# BRGTC6_Dual_Daughter.net
KiCad netlist of a schematic drawn in Altium Designer
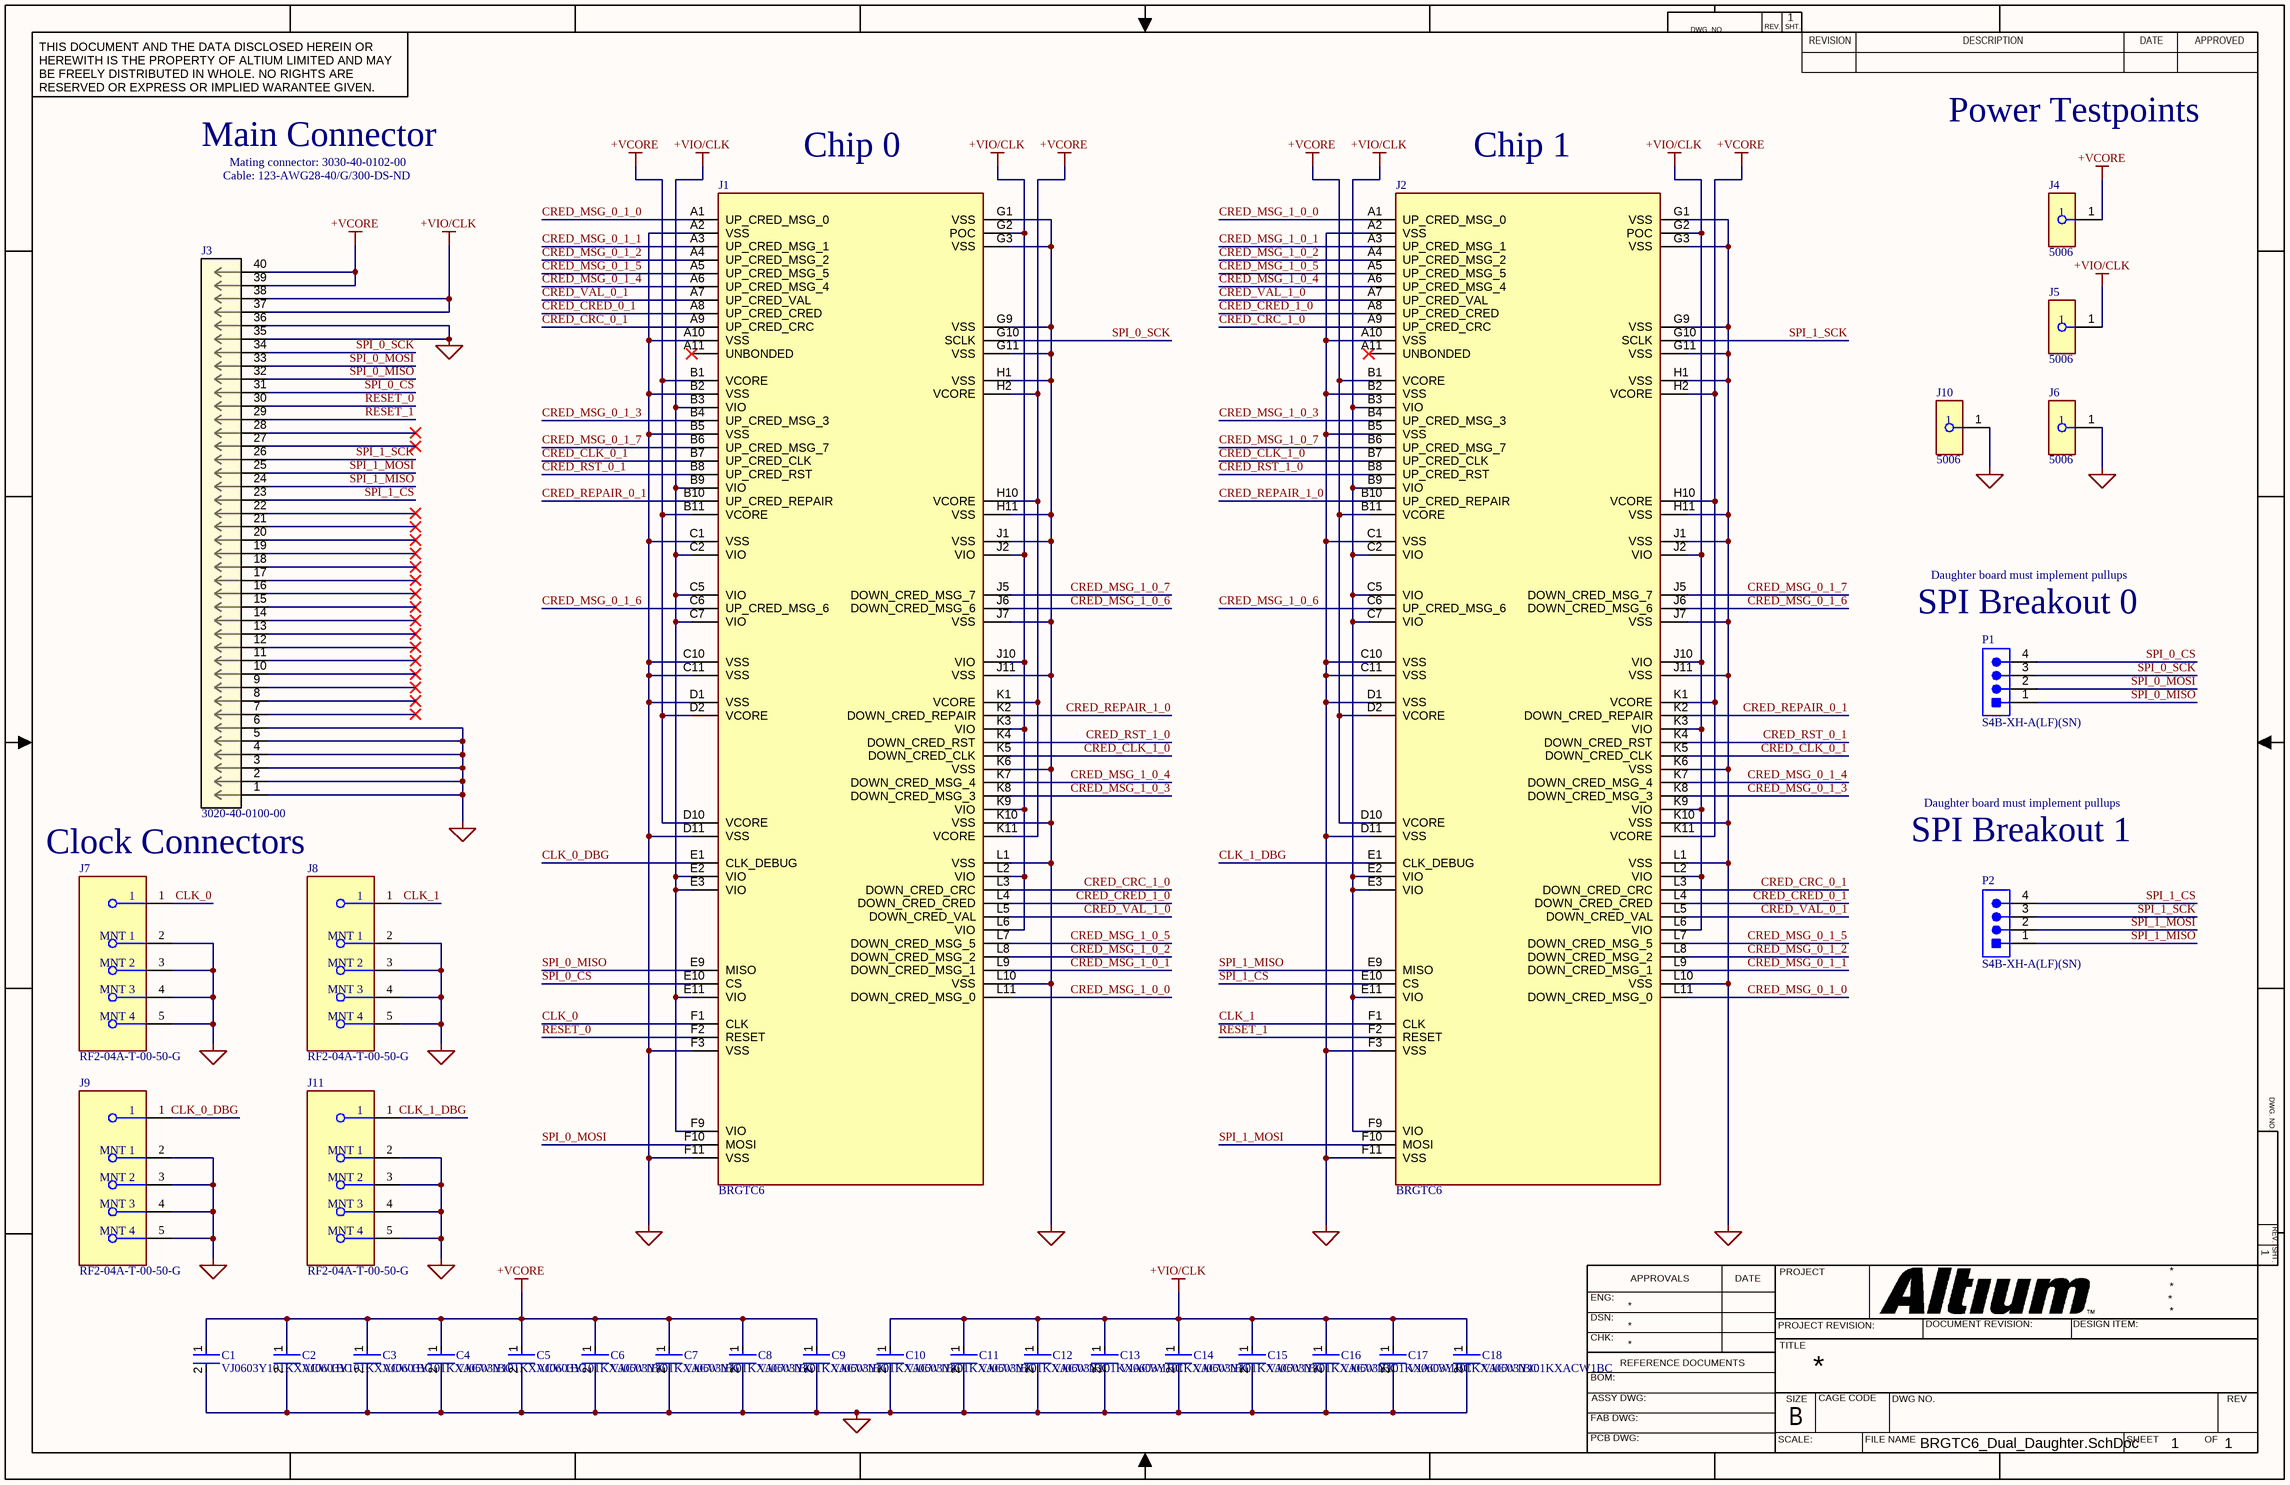
[diagram p0: BRGTC6_Dual_Daughter.SchDoc]

(export (version "E")
  (design (tool "Eeschema 10.0.6"))
  (components
    (comp (ref "C1")
      (value "VJ0603Y101KXACW1BC")
      (footprint "FP-CC0603-DA-MFG")
      (description "CAP CER 0.1UF 16V X7R 0603")
      (fields
        (field (name "OCTOPART") "https://octopart.com/cc0603krx7r7bb104-yageo-192941")
        (field (name "TOLERANCE") "0.1")
      )
      (libsource (lib "Altium Content Vault") (part "11868f565c42a9108669ba33697ecf6"))
    )
    (comp (ref "C2")
      (value "VJ0603Y101KXACW1BC")
      (footprint "FP-CC0603-DA-MFG")
      (description "CAP CER 0.1UF 16V X7R 0603")
      (fields
        (field (name "OCTOPART") "https://octopart.com/cc0603krx7r7bb104-yageo-192941")
        (field (name "TOLERANCE") "0.1")
      )
      (libsource (lib "Altium Content Vault") (part "11868f565c42a9108669ba33697ecf6"))
    )
    (comp (ref "C3")
      (value "VJ0603Y101KXACW1BC")
      (footprint "FP-CC0603-DA-MFG")
      (description "CAP CER 0.1UF 16V X7R 0603")
      (fields
        (field (name "OCTOPART") "https://octopart.com/cc0603krx7r7bb104-yageo-192941")
        (field (name "TOLERANCE") "0.1")
      )
      (libsource (lib "Altium Content Vault") (part "11868f565c42a9108669ba33697ecf6"))
    )
    (comp (ref "C4")
      (value "VJ0603Y101KXACW1BC")
      (footprint "FP-CC0603-DA-MFG")
      (description "CAP CER 0.1UF 16V X7R 0603")
      (fields
        (field (name "OCTOPART") "https://octopart.com/cc0603krx7r7bb104-yageo-192941")
        (field (name "TOLERANCE") "0.1")
      )
      (libsource (lib "Altium Content Vault") (part "11868f565c42a9108669ba33697ecf6"))
    )
    (comp (ref "C5")
      (value "VJ0603Y101KXACW1BC")
      (footprint "FP-CC0603-DA-MFG")
      (description "CAP CER 0.1UF 16V X7R 0603")
      (fields
        (field (name "OCTOPART") "https://octopart.com/cc0603krx7r7bb104-yageo-192941")
        (field (name "TOLERANCE") "0.1")
      )
      (libsource (lib "Altium Content Vault") (part "11868f565c42a9108669ba33697ecf6"))
    )
    (comp (ref "C6")
      (value "VJ0603Y101KXACW1BC")
      (footprint "FP-CC0603-DA-MFG")
      (description "CAP CER 0.1UF 16V X7R 0603")
      (fields
        (field (name "OCTOPART") "https://octopart.com/cc0603krx7r7bb104-yageo-192941")
        (field (name "TOLERANCE") "0.1")
      )
      (libsource (lib "Altium Content Vault") (part "11868f565c42a9108669ba33697ecf6"))
    )
    (comp (ref "C7")
      (value "VJ0603Y101KXACW1BC")
      (footprint "FP-CC0603-DA-MFG")
      (description "CAP CER 0.1UF 16V X7R 0603")
      (fields
        (field (name "OCTOPART") "https://octopart.com/cc0603krx7r7bb104-yageo-192941")
        (field (name "TOLERANCE") "0.1")
      )
      (libsource (lib "Altium Content Vault") (part "11868f565c42a9108669ba33697ecf6"))
    )
    (comp (ref "C8")
      (value "VJ0603Y101KXACW1BC")
      (footprint "FP-CC0603-DA-MFG")
      (description "CAP CER 0.1UF 16V X7R 0603")
      (fields
        (field (name "OCTOPART") "https://octopart.com/cc0603krx7r7bb104-yageo-192941")
        (field (name "TOLERANCE") "0.1")
      )
      (libsource (lib "Altium Content Vault") (part "11868f565c42a9108669ba33697ecf6"))
    )
    (comp (ref "C9")
      (value "VJ0603Y101KXACW1BC")
      (footprint "FP-CC0603-DA-MFG")
      (description "CAP CER 0.1UF 16V X7R 0603")
      (fields
        (field (name "OCTOPART") "https://octopart.com/cc0603krx7r7bb104-yageo-192941")
        (field (name "TOLERANCE") "0.1")
      )
      (libsource (lib "Altium Content Vault") (part "11868f565c42a9108669ba33697ecf6"))
    )
    (comp (ref "C10")
      (value "VJ0603Y101KXACW1BC")
      (footprint "FP-CC0603-DA-MFG")
      (description "CAP CER 0.1UF 16V X7R 0603")
      (fields
        (field (name "OCTOPART") "https://octopart.com/cc0603krx7r7bb104-yageo-192941")
        (field (name "TOLERANCE") "0.1")
      )
      (libsource (lib "Altium Content Vault") (part "11868f565c42a9108669ba33697ecf6"))
    )
    (comp (ref "C11")
      (value "VJ0603Y101KXACW1BC")
      (footprint "FP-CC0603-DA-MFG")
      (description "CAP CER 0.1UF 16V X7R 0603")
      (fields
        (field (name "OCTOPART") "https://octopart.com/cc0603krx7r7bb104-yageo-192941")
        (field (name "TOLERANCE") "0.1")
      )
      (libsource (lib "Altium Content Vault") (part "11868f565c42a9108669ba33697ecf6"))
    )
    (comp (ref "C12")
      (value "VJ0603Y101KXACW1BC")
      (footprint "FP-CC0603-DA-MFG")
      (description "CAP CER 0.1UF 16V X7R 0603")
      (fields
        (field (name "OCTOPART") "https://octopart.com/cc0603krx7r7bb104-yageo-192941")
        (field (name "TOLERANCE") "0.1")
      )
      (libsource (lib "Altium Content Vault") (part "11868f565c42a9108669ba33697ecf6"))
    )
    (comp (ref "C13")
      (value "VJ0603Y101KXACW1BC")
      (footprint "FP-CC0603-DA-MFG")
      (description "CAP CER 0.1UF 16V X7R 0603")
      (fields
        (field (name "OCTOPART") "https://octopart.com/cc0603krx7r7bb104-yageo-192941")
        (field (name "TOLERANCE") "0.1")
      )
      (libsource (lib "Altium Content Vault") (part "11868f565c42a9108669ba33697ecf6"))
    )
    (comp (ref "C14")
      (value "VJ0603Y101KXACW1BC")
      (footprint "FP-CC0603-DA-MFG")
      (description "CAP CER 0.1UF 16V X7R 0603")
      (fields
        (field (name "OCTOPART") "https://octopart.com/cc0603krx7r7bb104-yageo-192941")
        (field (name "TOLERANCE") "0.1")
      )
      (libsource (lib "Altium Content Vault") (part "11868f565c42a9108669ba33697ecf6"))
    )
    (comp (ref "C15")
      (value "VJ0603Y101KXACW1BC")
      (footprint "FP-CC0603-DA-MFG")
      (description "CAP CER 0.1UF 16V X7R 0603")
      (fields
        (field (name "OCTOPART") "https://octopart.com/cc0603krx7r7bb104-yageo-192941")
        (field (name "TOLERANCE") "0.1")
      )
      (libsource (lib "Altium Content Vault") (part "11868f565c42a9108669ba33697ecf6"))
    )
    (comp (ref "C16")
      (value "VJ0603Y101KXACW1BC")
      (footprint "FP-CC0603-DA-MFG")
      (description "CAP CER 0.1UF 16V X7R 0603")
      (fields
        (field (name "OCTOPART") "https://octopart.com/cc0603krx7r7bb104-yageo-192941")
        (field (name "TOLERANCE") "0.1")
      )
      (libsource (lib "Altium Content Vault") (part "11868f565c42a9108669ba33697ecf6"))
    )
    (comp (ref "C17")
      (value "VJ0603Y101KXACW1BC")
      (footprint "FP-CC0603-DA-MFG")
      (description "CAP CER 0.1UF 16V X7R 0603")
      (fields
        (field (name "OCTOPART") "https://octopart.com/cc0603krx7r7bb104-yageo-192941")
        (field (name "TOLERANCE") "0.1")
      )
      (libsource (lib "Altium Content Vault") (part "11868f565c42a9108669ba33697ecf6"))
    )
    (comp (ref "C18")
      (value "VJ0603Y101KXACW1BC")
      (footprint "FP-CC0603-DA-MFG")
      (description "CAP CER 0.1UF 16V X7R 0603")
      (fields
        (field (name "OCTOPART") "https://octopart.com/cc0603krx7r7bb104-yageo-192941")
        (field (name "TOLERANCE") "0.1")
      )
      (libsource (lib "Altium Content Vault") (part "11868f565c42a9108669ba33697ecf6"))
    )
    (comp (ref "J1")
      (value "BRGTC6")
      (footprint "3M_200-6311-9UN-1900")
      (description "121 _11 x 11_ Pos PGA, ZIF _ZIP_ Socket Gold Through Hole")
      (fields (field (name "DIGI-KEY_PART_NUMBER") "3M5067-ND") (field (name "MF") "3M"))
      (libsource (lib "BRGTC6") (part "200-6311-9UN-1900"))
    )
    (comp (ref "J2")
      (value "BRGTC6")
      (footprint "3M_200-6311-9UN-1900")
      (description "121 _11 x 11_ Pos PGA, ZIF _ZIP_ Socket Gold Through Hole")
      (fields (field (name "DIGI-KEY_PART_NUMBER") "3M5067-ND") (field (name "MF") "3M"))
      (libsource (lib "BRGTC6") (part "200-6311-9UN-1900"))
    )
    (comp (ref "J3")
      (value "3020-40-0100-00")
      (footprint "CONN_3020-40-0100-00_CNC")
      (description "No Description Available")
      (libsource (lib "3020-40-0100-00") (part "3020-40-0100-00"))
    )
    (comp (ref "J4")
      (value "5006")
      (footprint "FP-5006-MFG")
      (description "PC TEST POINT COMPACT BLACK")
      (libsource (lib "Altium Content Vault") (part "98815daf2f2c152b0c43f5ab9800df6"))
    )
    (comp (ref "J5")
      (value "5006")
      (footprint "FP-5006-MFG")
      (description "PC TEST POINT COMPACT BLACK")
      (libsource (lib "Altium Content Vault") (part "98815daf2f2c152b0c43f5ab9800df6"))
    )
    (comp (ref "J6")
      (value "5006")
      (footprint "FP-5006-MFG")
      (description "PC TEST POINT COMPACT BLACK")
      (libsource (lib "Altium Content Vault") (part "98815daf2f2c152b0c43f5ab9800df6"))
    )
    (comp (ref "J7")
      (value "RF2-04A-T-00-50-G")
      (footprint "FP-RF2-04A-T-00-50-G-MFG")
      (description "CONN SMA JACK STR 50 OHM PCB")
      (libsource (lib "Altium Content Vault") (part "c65b8a639cdaef1819ea20b5466f8fa"))
    )
    (comp (ref "J8")
      (value "RF2-04A-T-00-50-G")
      (footprint "FP-RF2-04A-T-00-50-G-MFG")
      (description "CONN SMA JACK STR 50 OHM PCB")
      (libsource (lib "Altium Content Vault") (part "c65b8a639cdaef1819ea20b5466f8fa"))
    )
    (comp (ref "J9")
      (value "RF2-04A-T-00-50-G")
      (footprint "FP-RF2-04A-T-00-50-G-MFG")
      (description "CONN SMA JACK STR 50 OHM PCB")
      (libsource (lib "Altium Content Vault") (part "c65b8a639cdaef1819ea20b5466f8fa"))
    )
    (comp (ref "J10")
      (value "5006")
      (footprint "FP-5006-MFG")
      (description "PC TEST POINT COMPACT BLACK")
      (libsource (lib "Altium Content Vault") (part "98815daf2f2c152b0c43f5ab9800df6"))
    )
    (comp (ref "J11")
      (value "RF2-04A-T-00-50-G")
      (footprint "FP-RF2-04A-T-00-50-G-MFG")
      (description "CONN SMA JACK STR 50 OHM PCB")
      (libsource (lib "Altium Content Vault") (part "c65b8a639cdaef1819ea20b5466f8fa"))
    )
    (comp (ref "P1")
      (value "S4B-XH-A(LF)(SN)")
      (footprint "JST-S4B-XH-A(LF)(SN)_V")
      (libsource (lib "Altium Content Vault") (part "CN-1P-M-R4"))
    )
    (comp (ref "P2")
      (value "S4B-XH-A(LF)(SN)")
      (footprint "JST-S4B-XH-A(LF)(SN)_V")
      (libsource (lib "Altium Content Vault") (part "CN-1P-M-R4"))
    )
  )
  (nets
    (net (code "1") (name "+VCORE") (class "Default")
      (node (ref "C1") (pin "1") (pinfunction "1_1") (pintype "passive"))
      (node (ref "C2") (pin "1") (pinfunction "1_1") (pintype "passive"))
      (node (ref "C3") (pin "1") (pinfunction "1_1") (pintype "passive"))
      (node (ref "C4") (pin "1") (pinfunction "1_1") (pintype "passive"))
      (node (ref "C5") (pin "1") (pinfunction "1_1") (pintype "passive"))
      (node (ref "C6") (pin "1") (pinfunction "1_1") (pintype "passive"))
      (node (ref "C7") (pin "1") (pinfunction "1_1") (pintype "passive"))
      (node (ref "C8") (pin "1") (pinfunction "1_1") (pintype "passive"))
      (node (ref "C9") (pin "1") (pinfunction "1_1") (pintype "passive"))
      (node (ref "J1") (pin "B1") (pinfunction "VCORE_B1") (pintype "passive"))
      (node (ref "J1") (pin "B11") (pinfunction "VCORE_B11") (pintype "passive"))
      (node (ref "J1") (pin "D10") (pinfunction "VCORE_D10") (pintype "passive"))
      (node (ref "J1") (pin "D2") (pinfunction "VCORE_D2") (pintype "passive"))
      (node (ref "J1") (pin "H10") (pinfunction "VCORE_H10") (pintype "passive"))
      (node (ref "J1") (pin "H2") (pinfunction "VCORE_H2") (pintype "passive"))
      (node (ref "J1") (pin "K1") (pinfunction "VCORE_K1") (pintype "passive"))
      (node (ref "J1") (pin "K11") (pinfunction "VCORE_K11") (pintype "passive"))
      (node (ref "J2") (pin "B1") (pinfunction "VCORE_B1") (pintype "passive"))
      (node (ref "J2") (pin "B11") (pinfunction "VCORE_B11") (pintype "passive"))
      (node (ref "J2") (pin "D10") (pinfunction "VCORE_D10") (pintype "passive"))
      (node (ref "J2") (pin "D2") (pinfunction "VCORE_D2") (pintype "passive"))
      (node (ref "J2") (pin "H10") (pinfunction "VCORE_H10") (pintype "passive"))
      (node (ref "J2") (pin "H2") (pinfunction "VCORE_H2") (pintype "passive"))
      (node (ref "J2") (pin "K1") (pinfunction "VCORE_K1") (pintype "passive"))
      (node (ref "J2") (pin "K11") (pinfunction "VCORE_K11") (pintype "passive"))
      (node (ref "J3") (pin "39") (pinfunction "39_39") (pintype "passive"))
      (node (ref "J3") (pin "40") (pinfunction "40_40") (pintype "passive"))
      (node (ref "J4") (pin "1") (pinfunction "1_1") (pintype "passive"))
    )
    (net (code "2") (name "+VIO{slash}CLK") (class "Default")
      (node (ref "C10") (pin "1") (pinfunction "1_1") (pintype "passive"))
      (node (ref "C11") (pin "1") (pinfunction "1_1") (pintype "passive"))
      (node (ref "C12") (pin "1") (pinfunction "1_1") (pintype "passive"))
      (node (ref "C13") (pin "1") (pinfunction "1_1") (pintype "passive"))
      (node (ref "C14") (pin "1") (pinfunction "1_1") (pintype "passive"))
      (node (ref "C15") (pin "1") (pinfunction "1_1") (pintype "passive"))
      (node (ref "C16") (pin "1") (pinfunction "1_1") (pintype "passive"))
      (node (ref "C17") (pin "1") (pinfunction "1_1") (pintype "passive"))
      (node (ref "C18") (pin "1") (pinfunction "1_1") (pintype "passive"))
      (node (ref "J1") (pin "B3") (pinfunction "VIO_B3") (pintype "passive"))
      (node (ref "J1") (pin "B9") (pinfunction "VIO_B9") (pintype "passive"))
      (node (ref "J1") (pin "C2") (pinfunction "VIO_C2") (pintype "passive"))
      (node (ref "J1") (pin "C5") (pinfunction "VIO_C5") (pintype "passive"))
      (node (ref "J1") (pin "C7") (pinfunction "VIO_C7") (pintype "passive"))
      (node (ref "J1") (pin "E11") (pinfunction "VIO_E11") (pintype "passive"))
      (node (ref "J1") (pin "E2") (pinfunction "VIO_E2") (pintype "passive"))
      (node (ref "J1") (pin "E3") (pinfunction "VIO_E3") (pintype "passive"))
      (node (ref "J1") (pin "F9") (pinfunction "VIO_F9") (pintype "passive"))
      (node (ref "J1") (pin "G2") (pinfunction "POC_G2") (pintype "passive"))
      (node (ref "J1") (pin "J10") (pinfunction "VIO_J10") (pintype "passive"))
      (node (ref "J1") (pin "J2") (pinfunction "VIO_J2") (pintype "passive"))
      (node (ref "J1") (pin "K3") (pinfunction "VIO_K3") (pintype "passive"))
      (node (ref "J1") (pin "K9") (pinfunction "VIO_K9") (pintype "passive"))
      (node (ref "J1") (pin "L2") (pinfunction "VIO_L2") (pintype "passive"))
      (node (ref "J1") (pin "L6") (pinfunction "VIO_L6") (pintype "passive"))
      (node (ref "J2") (pin "B3") (pinfunction "VIO_B3") (pintype "passive"))
      (node (ref "J2") (pin "B9") (pinfunction "VIO_B9") (pintype "passive"))
      (node (ref "J2") (pin "C2") (pinfunction "VIO_C2") (pintype "passive"))
      (node (ref "J2") (pin "C5") (pinfunction "VIO_C5") (pintype "passive"))
      (node (ref "J2") (pin "C7") (pinfunction "VIO_C7") (pintype "passive"))
      (node (ref "J2") (pin "E11") (pinfunction "VIO_E11") (pintype "passive"))
      (node (ref "J2") (pin "E2") (pinfunction "VIO_E2") (pintype "passive"))
      (node (ref "J2") (pin "E3") (pinfunction "VIO_E3") (pintype "passive"))
      (node (ref "J2") (pin "F9") (pinfunction "VIO_F9") (pintype "passive"))
      (node (ref "J2") (pin "G2") (pinfunction "POC_G2") (pintype "passive"))
      (node (ref "J2") (pin "J10") (pinfunction "VIO_J10") (pintype "passive"))
      (node (ref "J2") (pin "J2") (pinfunction "VIO_J2") (pintype "passive"))
      (node (ref "J2") (pin "K3") (pinfunction "VIO_K3") (pintype "passive"))
      (node (ref "J2") (pin "K9") (pinfunction "VIO_K9") (pintype "passive"))
      (node (ref "J2") (pin "L2") (pinfunction "VIO_L2") (pintype "passive"))
      (node (ref "J2") (pin "L6") (pinfunction "VIO_L6") (pintype "passive"))
      (node (ref "J3") (pin "37") (pinfunction "37_37") (pintype "passive"))
      (node (ref "J3") (pin "38") (pinfunction "38_38") (pintype "passive"))
      (node (ref "J5") (pin "1") (pinfunction "1_1") (pintype "passive"))
    )
    (net (code "3") (name "/CLK_0") (class "Default")
      (node (ref "J1") (pin "F1") (pinfunction "CLK_F1") (pintype "passive"))
      (node (ref "J7") (pin "1") (pinfunction "1_1") (pintype "passive"))
    )
    (net (code "4") (name "/CLK_0_DBG") (class "Default")
      (node (ref "J1") (pin "E1") (pinfunction "CLK_DEBUG_E1") (pintype "passive"))
      (node (ref "J9") (pin "1") (pinfunction "1_1") (pintype "passive"))
    )
    (net (code "5") (name "/CLK_1") (class "Default")
      (node (ref "J2") (pin "F1") (pinfunction "CLK_F1") (pintype "passive"))
      (node (ref "J8") (pin "1") (pinfunction "1_1") (pintype "passive"))
    )
    (net (code "6") (name "/CLK_1_DBG") (class "Default")
      (node (ref "J11") (pin "1") (pinfunction "1_1") (pintype "passive"))
      (node (ref "J2") (pin "E1") (pinfunction "CLK_DEBUG_E1") (pintype "passive"))
    )
    (net (code "7") (name "/CRED_CLK_0_1") (class "Default")
      (node (ref "J1") (pin "B7") (pinfunction "UP_CRED_CLK_B7") (pintype "passive"))
      (node (ref "J2") (pin "K5") (pinfunction "DOWN_CRED_CLK_K5") (pintype "passive"))
    )
    (net (code "8") (name "/CRED_CLK_1_0") (class "Default")
      (node (ref "J1") (pin "K5") (pinfunction "DOWN_CRED_CLK_K5") (pintype "passive"))
      (node (ref "J2") (pin "B7") (pinfunction "UP_CRED_CLK_B7") (pintype "passive"))
    )
    (net (code "9") (name "/CRED_CRC_0_1") (class "Default")
      (node (ref "J1") (pin "A9") (pinfunction "UP_CRED_CRC_A9") (pintype "passive"))
      (node (ref "J2") (pin "L3") (pinfunction "DOWN_CRED_CRC_L3") (pintype "passive"))
    )
    (net (code "10") (name "/CRED_CRC_1_0") (class "Default")
      (node (ref "J1") (pin "L3") (pinfunction "DOWN_CRED_CRC_L3") (pintype "passive"))
      (node (ref "J2") (pin "A9") (pinfunction "UP_CRED_CRC_A9") (pintype "passive"))
    )
    (net (code "11") (name "/CRED_CRED_0_1") (class "Default")
      (node (ref "J1") (pin "A8") (pinfunction "UP_CRED_CRED_A8") (pintype "passive"))
      (node (ref "J2") (pin "L4") (pinfunction "DOWN_CRED_CRED_L4") (pintype "passive"))
    )
    (net (code "12") (name "/CRED_CRED_1_0") (class "Default")
      (node (ref "J1") (pin "L4") (pinfunction "DOWN_CRED_CRED_L4") (pintype "passive"))
      (node (ref "J2") (pin "A8") (pinfunction "UP_CRED_CRED_A8") (pintype "passive"))
    )
    (net (code "13") (name "/CRED_MSG_0_1_0") (class "Default")
      (node (ref "J1") (pin "A1") (pinfunction "UP_CRED_MSG_0_A1") (pintype "passive"))
      (node (ref "J2") (pin "L11") (pinfunction "DOWN_CRED_MSG_0_L11") (pintype "passive"))
    )
    (net (code "14") (name "/CRED_MSG_0_1_1") (class "Default")
      (node (ref "J1") (pin "A3") (pinfunction "UP_CRED_MSG_1_A3") (pintype "passive"))
      (node (ref "J2") (pin "L9") (pinfunction "DOWN_CRED_MSG_1_L9") (pintype "passive"))
    )
    (net (code "15") (name "/CRED_MSG_0_1_2") (class "Default")
      (node (ref "J1") (pin "A4") (pinfunction "UP_CRED_MSG_2_A4") (pintype "passive"))
      (node (ref "J2") (pin "L8") (pinfunction "DOWN_CRED_MSG_2_L8") (pintype "passive"))
    )
    (net (code "16") (name "/CRED_MSG_0_1_3") (class "Default")
      (node (ref "J1") (pin "B4") (pinfunction "UP_CRED_MSG_3_B4") (pintype "passive"))
      (node (ref "J2") (pin "K8") (pinfunction "DOWN_CRED_MSG_3_K8") (pintype "passive"))
    )
    (net (code "17") (name "/CRED_MSG_0_1_4") (class "Default")
      (node (ref "J1") (pin "A6") (pinfunction "UP_CRED_MSG_4_A6") (pintype "passive"))
      (node (ref "J2") (pin "K7") (pinfunction "DOWN_CRED_MSG_4_K7") (pintype "passive"))
    )
    (net (code "18") (name "/CRED_MSG_0_1_5") (class "Default")
      (node (ref "J1") (pin "A5") (pinfunction "UP_CRED_MSG_5_A5") (pintype "passive"))
      (node (ref "J2") (pin "L7") (pinfunction "DOWN_CRED_MSG_5_L7") (pintype "passive"))
    )
    (net (code "19") (name "/CRED_MSG_0_1_6") (class "Default")
      (node (ref "J1") (pin "C6") (pinfunction "UP_CRED_MSG_6_C6") (pintype "passive"))
      (node (ref "J2") (pin "J6") (pinfunction "DOWN_CRED_MSG_6_J6") (pintype "passive"))
    )
    (net (code "20") (name "/CRED_MSG_0_1_7") (class "Default")
      (node (ref "J1") (pin "B6") (pinfunction "UP_CRED_MSG_7_B6") (pintype "passive"))
      (node (ref "J2") (pin "J5") (pinfunction "DOWN_CRED_MSG_7_J5") (pintype "passive"))
    )
    (net (code "21") (name "/CRED_MSG_1_0_0") (class "Default")
      (node (ref "J1") (pin "L11") (pinfunction "DOWN_CRED_MSG_0_L11") (pintype "passive"))
      (node (ref "J2") (pin "A1") (pinfunction "UP_CRED_MSG_0_A1") (pintype "passive"))
    )
    (net (code "22") (name "/CRED_MSG_1_0_1") (class "Default")
      (node (ref "J1") (pin "L9") (pinfunction "DOWN_CRED_MSG_1_L9") (pintype "passive"))
      (node (ref "J2") (pin "A3") (pinfunction "UP_CRED_MSG_1_A3") (pintype "passive"))
    )
    (net (code "23") (name "/CRED_MSG_1_0_2") (class "Default")
      (node (ref "J1") (pin "L8") (pinfunction "DOWN_CRED_MSG_2_L8") (pintype "passive"))
      (node (ref "J2") (pin "A4") (pinfunction "UP_CRED_MSG_2_A4") (pintype "passive"))
    )
    (net (code "24") (name "/CRED_MSG_1_0_3") (class "Default")
      (node (ref "J1") (pin "K8") (pinfunction "DOWN_CRED_MSG_3_K8") (pintype "passive"))
      (node (ref "J2") (pin "B4") (pinfunction "UP_CRED_MSG_3_B4") (pintype "passive"))
    )
    (net (code "25") (name "/CRED_MSG_1_0_4") (class "Default")
      (node (ref "J1") (pin "K7") (pinfunction "DOWN_CRED_MSG_4_K7") (pintype "passive"))
      (node (ref "J2") (pin "A6") (pinfunction "UP_CRED_MSG_4_A6") (pintype "passive"))
    )
    (net (code "26") (name "/CRED_MSG_1_0_5") (class "Default")
      (node (ref "J1") (pin "L7") (pinfunction "DOWN_CRED_MSG_5_L7") (pintype "passive"))
      (node (ref "J2") (pin "A5") (pinfunction "UP_CRED_MSG_5_A5") (pintype "passive"))
    )
    (net (code "27") (name "/CRED_MSG_1_0_6") (class "Default")
      (node (ref "J1") (pin "J6") (pinfunction "DOWN_CRED_MSG_6_J6") (pintype "passive"))
      (node (ref "J2") (pin "C6") (pinfunction "UP_CRED_MSG_6_C6") (pintype "passive"))
    )
    (net (code "28") (name "/CRED_MSG_1_0_7") (class "Default")
      (node (ref "J1") (pin "J5") (pinfunction "DOWN_CRED_MSG_7_J5") (pintype "passive"))
      (node (ref "J2") (pin "B6") (pinfunction "UP_CRED_MSG_7_B6") (pintype "passive"))
    )
    (net (code "29") (name "/CRED_REPAIR_0_1") (class "Default")
      (node (ref "J1") (pin "B10") (pinfunction "UP_CRED_REPAIR_B10") (pintype "passive"))
      (node (ref "J2") (pin "K2") (pinfunction "DOWN_CRED_REPAIR_K2") (pintype "passive"))
    )
    (net (code "30") (name "/CRED_REPAIR_1_0") (class "Default")
      (node (ref "J1") (pin "K2") (pinfunction "DOWN_CRED_REPAIR_K2") (pintype "passive"))
      (node (ref "J2") (pin "B10") (pinfunction "UP_CRED_REPAIR_B10") (pintype "passive"))
    )
    (net (code "31") (name "/CRED_RST_0_1") (class "Default")
      (node (ref "J1") (pin "B8") (pinfunction "UP_CRED_RST_B8") (pintype "passive"))
      (node (ref "J2") (pin "K4") (pinfunction "DOWN_CRED_RST_K4") (pintype "passive"))
    )
    (net (code "32") (name "/CRED_RST_1_0") (class "Default")
      (node (ref "J1") (pin "K4") (pinfunction "DOWN_CRED_RST_K4") (pintype "passive"))
      (node (ref "J2") (pin "B8") (pinfunction "UP_CRED_RST_B8") (pintype "passive"))
    )
    (net (code "33") (name "/CRED_VAL_0_1") (class "Default")
      (node (ref "J1") (pin "A7") (pinfunction "UP_CRED_VAL_A7") (pintype "passive"))
      (node (ref "J2") (pin "L5") (pinfunction "DOWN_CRED_VAL_L5") (pintype "passive"))
    )
    (net (code "34") (name "/CRED_VAL_1_0") (class "Default")
      (node (ref "J1") (pin "L5") (pinfunction "DOWN_CRED_VAL_L5") (pintype "passive"))
      (node (ref "J2") (pin "A7") (pinfunction "UP_CRED_VAL_A7") (pintype "passive"))
    )
    (net (code "35") (name "/RESET_0") (class "Default")
      (node (ref "J1") (pin "F2") (pinfunction "RESET_F2") (pintype "passive"))
      (node (ref "J3") (pin "30") (pinfunction "30_30") (pintype "passive"))
    )
    (net (code "36") (name "/RESET_1") (class "Default")
      (node (ref "J2") (pin "F2") (pinfunction "RESET_F2") (pintype "passive"))
      (node (ref "J3") (pin "29") (pinfunction "29_29") (pintype "passive"))
    )
    (net (code "37") (name "/SPI_0_CS") (class "Default")
      (node (ref "J1") (pin "E10") (pinfunction "CS_E10") (pintype "passive"))
      (node (ref "J3") (pin "31") (pinfunction "31_31") (pintype "passive"))
      (node (ref "P1") (pin "4") (pinfunction "4_4") (pintype "passive"))
    )
    (net (code "38") (name "/SPI_0_MISO") (class "Default")
      (node (ref "J1") (pin "E9") (pinfunction "MISO_E9") (pintype "passive"))
      (node (ref "J3") (pin "32") (pinfunction "32_32") (pintype "passive"))
      (node (ref "P1") (pin "1") (pinfunction "1_1") (pintype "passive"))
    )
    (net (code "39") (name "/SPI_0_MOSI") (class "Default")
      (node (ref "J1") (pin "F10") (pinfunction "MOSI_F10") (pintype "passive"))
      (node (ref "J3") (pin "33") (pinfunction "33_33") (pintype "passive"))
      (node (ref "P1") (pin "2") (pinfunction "2_2") (pintype "passive"))
    )
    (net (code "40") (name "/SPI_0_SCK") (class "Default")
      (node (ref "J1") (pin "G10") (pinfunction "SCLK_G10") (pintype "passive"))
      (node (ref "J3") (pin "34") (pinfunction "34_34") (pintype "passive"))
      (node (ref "P1") (pin "3") (pinfunction "3_3") (pintype "passive"))
    )
    (net (code "41") (name "/SPI_1_CS") (class "Default")
      (node (ref "J2") (pin "E10") (pinfunction "CS_E10") (pintype "passive"))
      (node (ref "J3") (pin "23") (pinfunction "23_23") (pintype "passive"))
      (node (ref "P2") (pin "4") (pinfunction "4_4") (pintype "passive"))
    )
    (net (code "42") (name "/SPI_1_MISO") (class "Default")
      (node (ref "J2") (pin "E9") (pinfunction "MISO_E9") (pintype "passive"))
      (node (ref "J3") (pin "24") (pinfunction "24_24") (pintype "passive"))
      (node (ref "P2") (pin "1") (pinfunction "1_1") (pintype "passive"))
    )
    (net (code "43") (name "/SPI_1_MOSI") (class "Default")
      (node (ref "J2") (pin "F10") (pinfunction "MOSI_F10") (pintype "passive"))
      (node (ref "J3") (pin "25") (pinfunction "25_25") (pintype "passive"))
      (node (ref "P2") (pin "2") (pinfunction "2_2") (pintype "passive"))
    )
    (net (code "44") (name "/SPI_1_SCK") (class "Default")
      (node (ref "J2") (pin "G10") (pinfunction "SCLK_G10") (pintype "passive"))
      (node (ref "J3") (pin "26") (pinfunction "26_26") (pintype "passive"))
      (node (ref "P2") (pin "3") (pinfunction "3_3") (pintype "passive"))
    )
    (net (code "45") (name "GND") (class "Default")
      (node (ref "C1") (pin "2") (pinfunction "2_2") (pintype "passive"))
      (node (ref "C10") (pin "2") (pinfunction "2_2") (pintype "passive"))
      (node (ref "C11") (pin "2") (pinfunction "2_2") (pintype "passive"))
      (node (ref "C12") (pin "2") (pinfunction "2_2") (pintype "passive"))
      (node (ref "C13") (pin "2") (pinfunction "2_2") (pintype "passive"))
      (node (ref "C14") (pin "2") (pinfunction "2_2") (pintype "passive"))
      (node (ref "C15") (pin "2") (pinfunction "2_2") (pintype "passive"))
      (node (ref "C16") (pin "2") (pinfunction "2_2") (pintype "passive"))
      (node (ref "C17") (pin "2") (pinfunction "2_2") (pintype "passive"))
      (node (ref "C18") (pin "2") (pinfunction "2_2") (pintype "passive"))
      (node (ref "C2") (pin "2") (pinfunction "2_2") (pintype "passive"))
      (node (ref "C3") (pin "2") (pinfunction "2_2") (pintype "passive"))
      (node (ref "C4") (pin "2") (pinfunction "2_2") (pintype "passive"))
      (node (ref "C5") (pin "2") (pinfunction "2_2") (pintype "passive"))
      (node (ref "C6") (pin "2") (pinfunction "2_2") (pintype "passive"))
      (node (ref "C7") (pin "2") (pinfunction "2_2") (pintype "passive"))
      (node (ref "C8") (pin "2") (pinfunction "2_2") (pintype "passive"))
      (node (ref "C9") (pin "2") (pinfunction "2_2") (pintype "passive"))
      (node (ref "J1") (pin "A10") (pinfunction "VSS_A10") (pintype "passive"))
      (node (ref "J1") (pin "A2") (pinfunction "VSS_A2") (pintype "passive"))
      (node (ref "J1") (pin "B2") (pinfunction "VSS_B2") (pintype "passive"))
      (node (ref "J1") (pin "B5") (pinfunction "VSS_B5") (pintype "passive"))
      (node (ref "J1") (pin "C1") (pinfunction "VSS_C1") (pintype "passive"))
      (node (ref "J1") (pin "C10") (pinfunction "VSS_C10") (pintype "passive"))
      (node (ref "J1") (pin "C11") (pinfunction "VSS_C11") (pintype "passive"))
      (node (ref "J1") (pin "D1") (pinfunction "VSS_D1") (pintype "passive"))
      (node (ref "J1") (pin "D11") (pinfunction "VSS_D11") (pintype "passive"))
      (node (ref "J1") (pin "F11") (pinfunction "VSS_F11") (pintype "passive"))
      (node (ref "J1") (pin "F3") (pinfunction "VSS_F3") (pintype "passive"))
      (node (ref "J1") (pin "G1") (pinfunction "VSS_G1") (pintype "passive"))
      (node (ref "J1") (pin "G11") (pinfunction "VSS_G11") (pintype "passive"))
      (node (ref "J1") (pin "G3") (pinfunction "VSS_G3") (pintype "passive"))
      (node (ref "J1") (pin "G9") (pinfunction "VSS_G9") (pintype "passive"))
      (node (ref "J1") (pin "H1") (pinfunction "VSS_H1") (pintype "passive"))
      (node (ref "J1") (pin "H11") (pinfunction "VSS_H11") (pintype "passive"))
      (node (ref "J1") (pin "J1") (pinfunction "VSS_J1") (pintype "passive"))
      (node (ref "J1") (pin "J11") (pinfunction "VSS_J11") (pintype "passive"))
      (node (ref "J1") (pin "J7") (pinfunction "VSS_J7") (pintype "passive"))
      (node (ref "J1") (pin "K10") (pinfunction "VSS_K10") (pintype "passive"))
      (node (ref "J1") (pin "K6") (pinfunction "VSS_K6") (pintype "passive"))
      (node (ref "J1") (pin "L1") (pinfunction "VSS_L1") (pintype "passive"))
      (node (ref "J1") (pin "L10") (pinfunction "VSS_L10") (pintype "passive"))
      (node (ref "J10") (pin "1") (pinfunction "1_1") (pintype "passive"))
      (node (ref "J11") (pin "2") (pinfunction "MNT_1_2") (pintype "passive"))
      (node (ref "J11") (pin "3") (pinfunction "MNT_2_3") (pintype "passive"))
      (node (ref "J11") (pin "4") (pinfunction "MNT_3_4") (pintype "passive"))
      (node (ref "J11") (pin "5") (pinfunction "MNT_4_5") (pintype "passive"))
      (node (ref "J2") (pin "A10") (pinfunction "VSS_A10") (pintype "passive"))
      (node (ref "J2") (pin "A2") (pinfunction "VSS_A2") (pintype "passive"))
      (node (ref "J2") (pin "B2") (pinfunction "VSS_B2") (pintype "passive"))
      (node (ref "J2") (pin "B5") (pinfunction "VSS_B5") (pintype "passive"))
      (node (ref "J2") (pin "C1") (pinfunction "VSS_C1") (pintype "passive"))
      (node (ref "J2") (pin "C10") (pinfunction "VSS_C10") (pintype "passive"))
      (node (ref "J2") (pin "C11") (pinfunction "VSS_C11") (pintype "passive"))
      (node (ref "J2") (pin "D1") (pinfunction "VSS_D1") (pintype "passive"))
      (node (ref "J2") (pin "D11") (pinfunction "VSS_D11") (pintype "passive"))
      (node (ref "J2") (pin "F11") (pinfunction "VSS_F11") (pintype "passive"))
      (node (ref "J2") (pin "F3") (pinfunction "VSS_F3") (pintype "passive"))
      (node (ref "J2") (pin "G1") (pinfunction "VSS_G1") (pintype "passive"))
      (node (ref "J2") (pin "G11") (pinfunction "VSS_G11") (pintype "passive"))
      (node (ref "J2") (pin "G3") (pinfunction "VSS_G3") (pintype "passive"))
      (node (ref "J2") (pin "G9") (pinfunction "VSS_G9") (pintype "passive"))
      (node (ref "J2") (pin "H1") (pinfunction "VSS_H1") (pintype "passive"))
      (node (ref "J2") (pin "H11") (pinfunction "VSS_H11") (pintype "passive"))
      (node (ref "J2") (pin "J1") (pinfunction "VSS_J1") (pintype "passive"))
      (node (ref "J2") (pin "J11") (pinfunction "VSS_J11") (pintype "passive"))
      (node (ref "J2") (pin "J7") (pinfunction "VSS_J7") (pintype "passive"))
      (node (ref "J2") (pin "K10") (pinfunction "VSS_K10") (pintype "passive"))
      (node (ref "J2") (pin "K6") (pinfunction "VSS_K6") (pintype "passive"))
      (node (ref "J2") (pin "L1") (pinfunction "VSS_L1") (pintype "passive"))
      (node (ref "J2") (pin "L10") (pinfunction "VSS_L10") (pintype "passive"))
      (node (ref "J3") (pin "1") (pinfunction "1_1") (pintype "passive"))
      (node (ref "J3") (pin "2") (pinfunction "2_2") (pintype "passive"))
      (node (ref "J3") (pin "3") (pinfunction "3_3") (pintype "passive"))
      (node (ref "J3") (pin "35") (pinfunction "35_35") (pintype "passive"))
      (node (ref "J3") (pin "36") (pinfunction "36_36") (pintype "passive"))
      (node (ref "J3") (pin "4") (pinfunction "4_4") (pintype "passive"))
      (node (ref "J3") (pin "5") (pinfunction "5_5") (pintype "passive"))
      (node (ref "J3") (pin "6") (pinfunction "6_6") (pintype "passive"))
      (node (ref "J6") (pin "1") (pinfunction "1_1") (pintype "passive"))
      (node (ref "J7") (pin "2") (pinfunction "MNT_1_2") (pintype "passive"))
      (node (ref "J7") (pin "3") (pinfunction "MNT_2_3") (pintype "passive"))
      (node (ref "J7") (pin "4") (pinfunction "MNT_3_4") (pintype "passive"))
      (node (ref "J7") (pin "5") (pinfunction "MNT_4_5") (pintype "passive"))
      (node (ref "J8") (pin "2") (pinfunction "MNT_1_2") (pintype "passive"))
      (node (ref "J8") (pin "3") (pinfunction "MNT_2_3") (pintype "passive"))
      (node (ref "J8") (pin "4") (pinfunction "MNT_3_4") (pintype "passive"))
      (node (ref "J8") (pin "5") (pinfunction "MNT_4_5") (pintype "passive"))
      (node (ref "J9") (pin "2") (pinfunction "MNT_1_2") (pintype "passive"))
      (node (ref "J9") (pin "3") (pinfunction "MNT_2_3") (pintype "passive"))
      (node (ref "J9") (pin "4") (pinfunction "MNT_3_4") (pintype "passive"))
      (node (ref "J9") (pin "5") (pinfunction "MNT_4_5") (pintype "passive"))
    )
    (net (code "46") (name "unconnected-(J1-UNBONDED-PadA11)") (class "Default")
      (node (ref "J1") (pin "A11") (pinfunction "UNBONDED_A11") (pintype "passive+no_connect"))
    )
    (net (code "47") (name "unconnected-(J2-UNBONDED-PadA11)") (class "Default")
      (node (ref "J2") (pin "A11") (pinfunction "UNBONDED_A11") (pintype "passive+no_connect"))
    )
    (net (code "48") (name "unconnected-(J3-Pad7)") (class "Default")
      (node (ref "J3") (pin "7") (pinfunction "7_7") (pintype "passive+no_connect"))
    )
    (net (code "49") (name "unconnected-(J3-Pad8)") (class "Default")
      (node (ref "J3") (pin "8") (pinfunction "8_8") (pintype "passive+no_connect"))
    )
    (net (code "50") (name "unconnected-(J3-Pad9)") (class "Default")
      (node (ref "J3") (pin "9") (pinfunction "9_9") (pintype "passive+no_connect"))
    )
    (net (code "51") (name "unconnected-(J3-Pad10)") (class "Default")
      (node (ref "J3") (pin "10") (pinfunction "10_10") (pintype "passive+no_connect"))
    )
    (net (code "52") (name "unconnected-(J3-Pad11)") (class "Default")
      (node (ref "J3") (pin "11") (pinfunction "11_11") (pintype "passive+no_connect"))
    )
    (net (code "53") (name "unconnected-(J3-Pad12)") (class "Default")
      (node (ref "J3") (pin "12") (pinfunction "12_12") (pintype "passive+no_connect"))
    )
    (net (code "54") (name "unconnected-(J3-Pad13)") (class "Default")
      (node (ref "J3") (pin "13") (pinfunction "13_13") (pintype "passive+no_connect"))
    )
    (net (code "55") (name "unconnected-(J3-Pad14)") (class "Default")
      (node (ref "J3") (pin "14") (pinfunction "14_14") (pintype "passive+no_connect"))
    )
    (net (code "56") (name "unconnected-(J3-Pad15)") (class "Default")
      (node (ref "J3") (pin "15") (pinfunction "15_15") (pintype "passive+no_connect"))
    )
    (net (code "57") (name "unconnected-(J3-Pad16)") (class "Default")
      (node (ref "J3") (pin "16") (pinfunction "16_16") (pintype "passive+no_connect"))
    )
    (net (code "58") (name "unconnected-(J3-Pad17)") (class "Default")
      (node (ref "J3") (pin "17") (pinfunction "17_17") (pintype "passive+no_connect"))
    )
    (net (code "59") (name "unconnected-(J3-Pad18)") (class "Default")
      (node (ref "J3") (pin "18") (pinfunction "18_18") (pintype "passive+no_connect"))
    )
    (net (code "60") (name "unconnected-(J3-Pad19)") (class "Default")
      (node (ref "J3") (pin "19") (pinfunction "19_19") (pintype "passive+no_connect"))
    )
    (net (code "61") (name "unconnected-(J3-Pad20)") (class "Default")
      (node (ref "J3") (pin "20") (pinfunction "20_20") (pintype "passive+no_connect"))
    )
    (net (code "62") (name "unconnected-(J3-Pad21)") (class "Default")
      (node (ref "J3") (pin "21") (pinfunction "21_21") (pintype "passive+no_connect"))
    )
    (net (code "63") (name "unconnected-(J3-Pad22)") (class "Default")
      (node (ref "J3") (pin "22") (pinfunction "22_22") (pintype "passive+no_connect"))
    )
    (net (code "64") (name "unconnected-(J3-Pad27)") (class "Default")
      (node (ref "J3") (pin "27") (pinfunction "27_27") (pintype "passive+no_connect"))
    )
    (net (code "65") (name "unconnected-(J3-Pad28)") (class "Default")
      (node (ref "J3") (pin "28") (pinfunction "28_28") (pintype "passive+no_connect"))
    )
  )
)
